# SCH_Orto-Idroponico_2021-11-15.net
KiCad netlist of a schematic drawn in EasyEDA
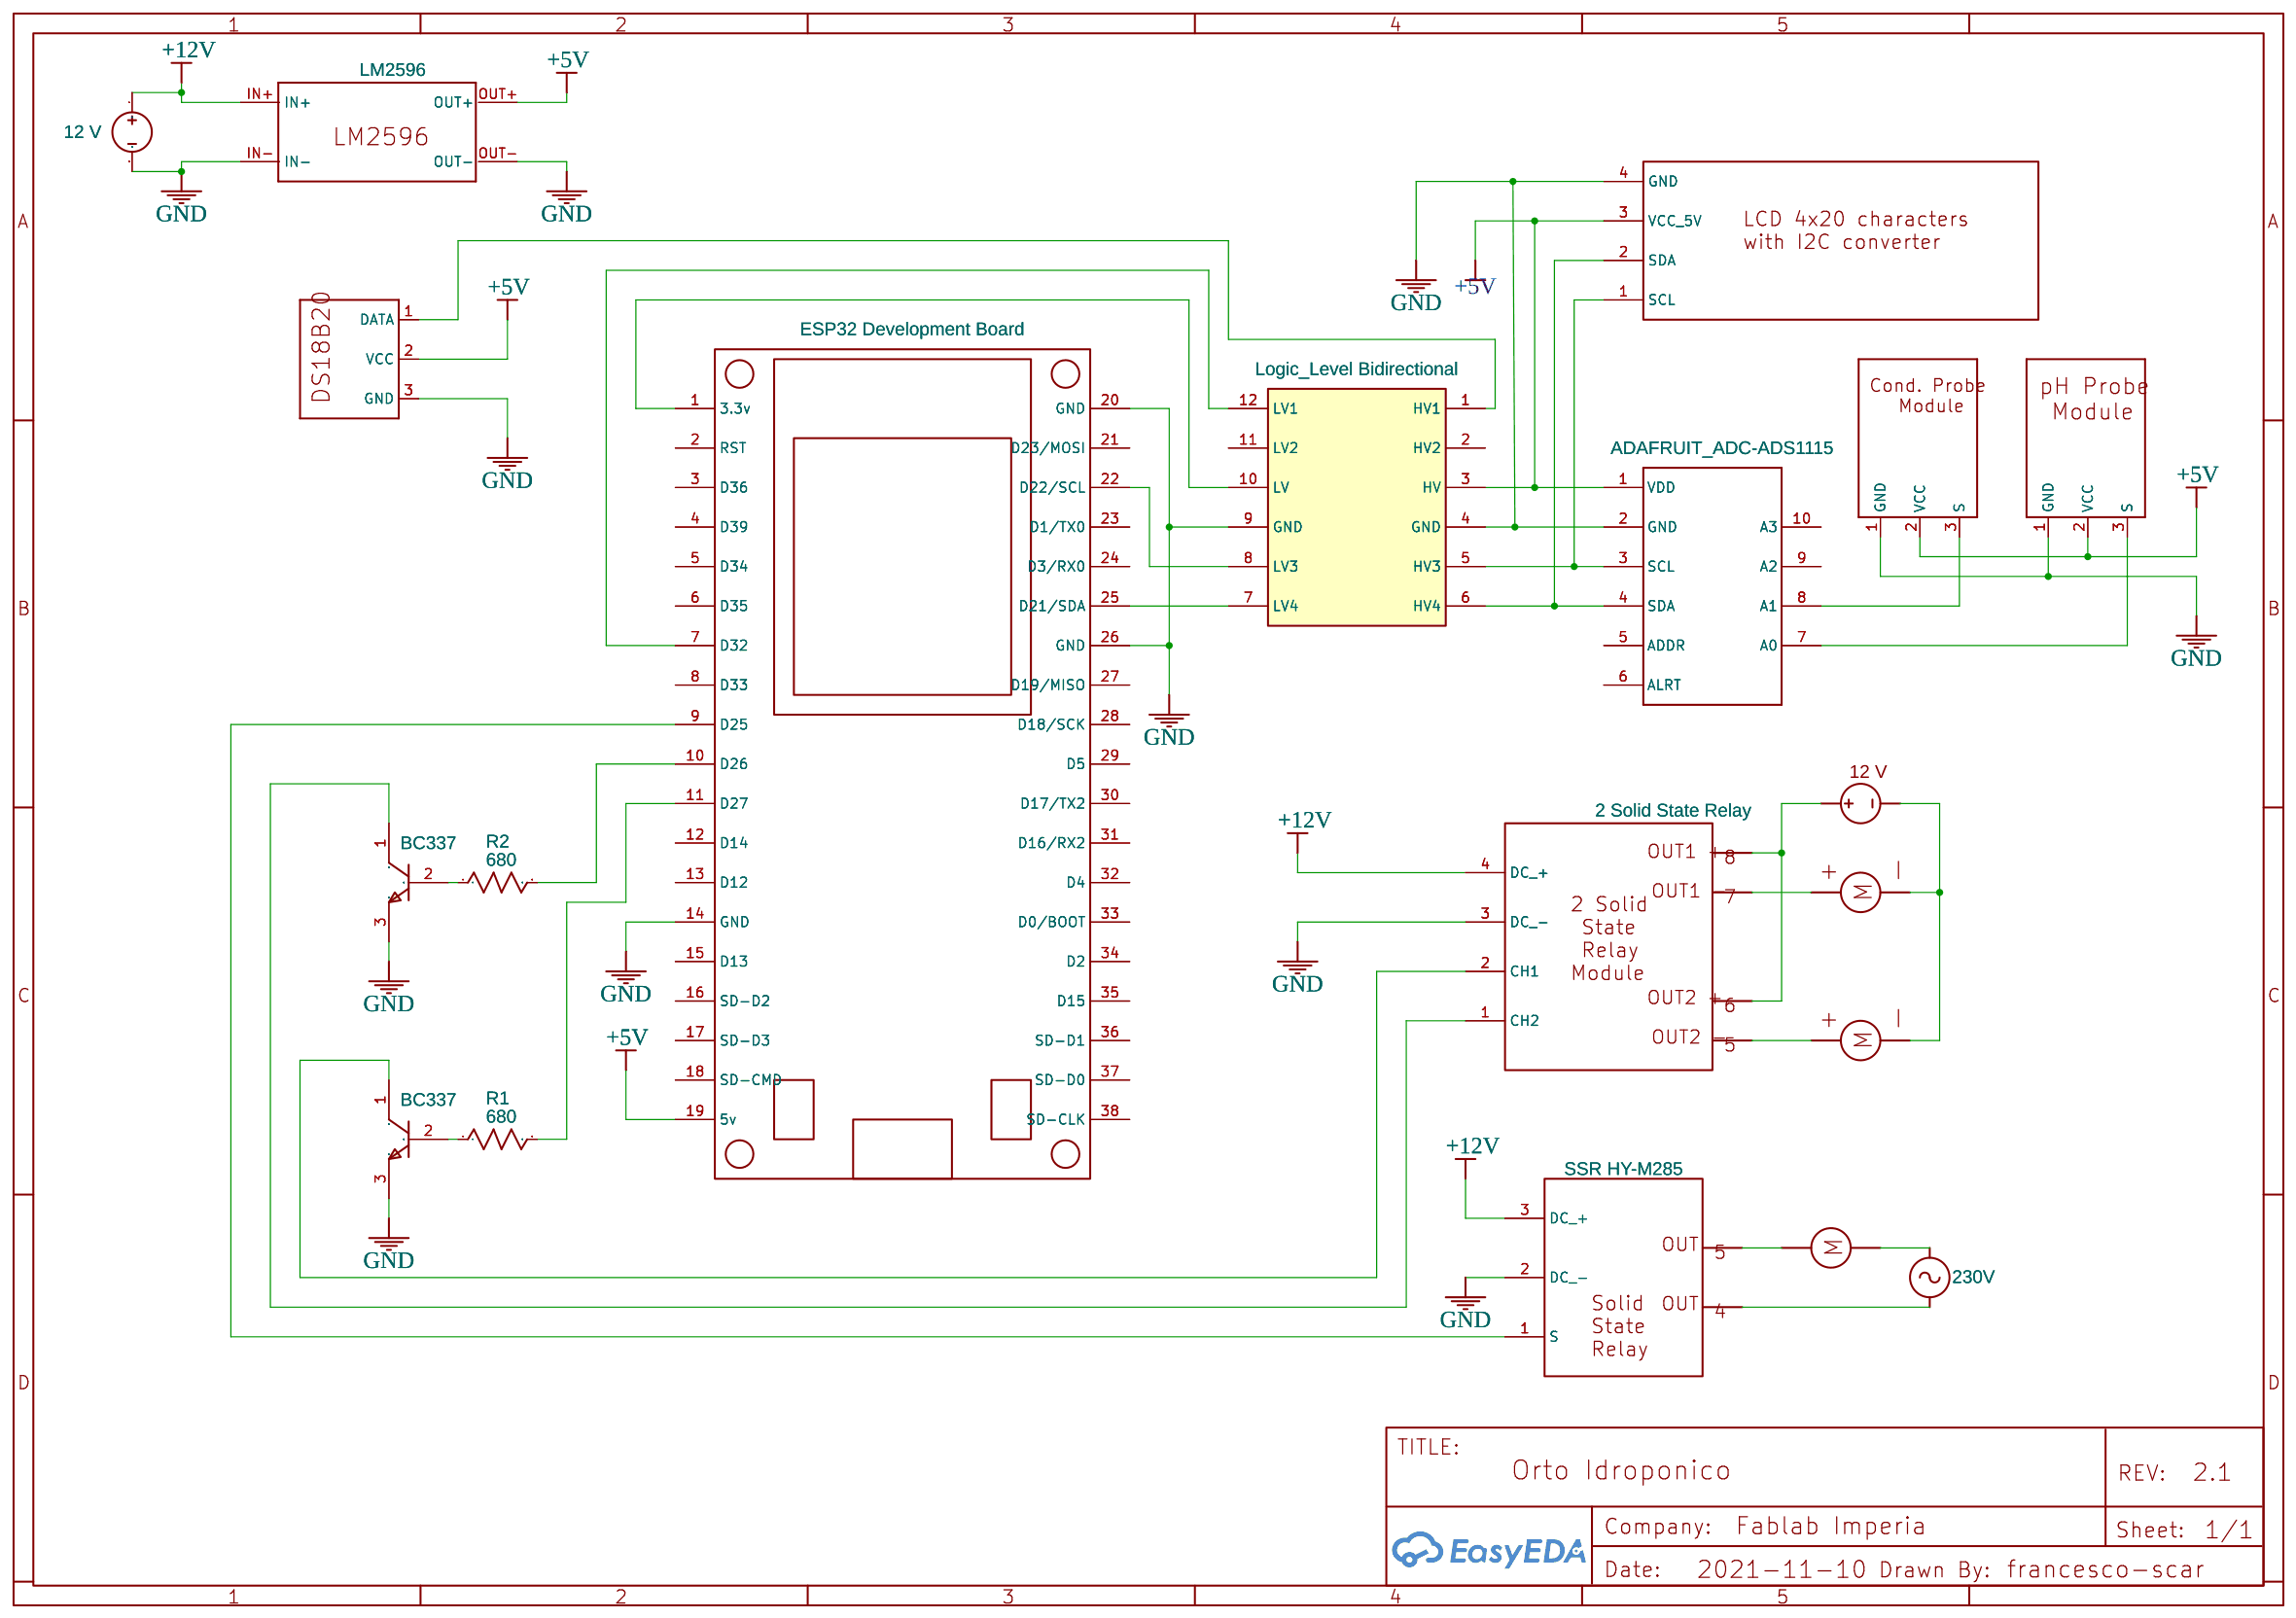
[diagram p0: schematic sheet]

(export (version "E")
  (design (tool "Eeschema 10.0.6"))
  (components
    (comp (ref "2") (value "ADAFRUIT_ADC-ADS1115") (libsource (lib "") (part "ADAFRUIT_ADC-ADS1115")))
    (comp (ref "230V") (value "AC source no pins") (libsource (lib "") (part "AC source no pins")))
    (comp (ref "P2")
      (value "Logic_Level Bidirectional")
      (libsource (lib "") (part "Logic_Level Bidirectional"))
    )
    (comp (ref "Q1") (value "BC337") (libsource (lib "") (part "BC337-40RL1G")))
    (comp (ref "Q2") (value "BC337") (libsource (lib "") (part "BC337-40RL1G")))
    (comp (ref "R1") (value "680") (libsource (lib "") (part "R_AXIAL-1.2_US")))
    (comp (ref "R2") (value "680") (libsource (lib "") (part "R_AXIAL-1.2_US")))
    (comp (ref "REG2") (value "LM2596") (libsource (lib "") (part "LM2596")))
    (comp (ref "T1") (value "DS18B20") (libsource (lib "") (part "DS18B20")))
    (comp (ref "T2") (value "pH probe module") (libsource (lib "") (part "pH probe module")))
    (comp (ref "T3")
      (value "conductivity probe module")
      (libsource (lib "") (part "conductivity probe module"))
    )
    (comp (ref "U1") (value "ESP32 Development Board") (libsource (lib "") (part "ESP32 Development Board")))
    (comp (ref "U2") (value "2 Solid State Relay") (libsource (lib "") (part "2 Solid State Relay")))
    (comp (ref "U3")
      (value "Nettigo LCD 4x20 I2C")
      (fields (field (name "BOM_Manufacturer Part") "2004A"))
      (libsource (lib "") (part "Nettigo LCD 4x20 I2C"))
    )
    (comp (ref "U4") (value "DC power source no pin") (libsource (lib "") (part "DC power source no pin")))
    (comp (ref "U5") (value "SSR HY-M285") (libsource (lib "") (part "Solid State Relay SSR HY-M285")))
    (comp (ref "U7") (value "DC Motor no pin") (libsource (lib "") (part "DC Motor no pin")))
    (comp (ref "U8") (value "DC Motor no pin") (libsource (lib "") (part "DC Motor no pin_1")))
    (comp (ref "U9") (value "DC Motor no pin") (libsource (lib "") (part "DC Motor no pin")))
    (comp (ref "V1") (value "12 V") (libsource (lib "") (part "DC Power Source")))
  )
  (nets
    (net (code "1") (name "+5V") (class "Default")
      (node (ref "2") (pin "1") (pinfunction "VDD_1") (pintype "bidirectional"))
      (node (ref "P2") (pin "3") (pinfunction "HV_3") (pintype "unspecified"))
      (node (ref "REG2") (pin "OUT+") (pinfunction "OUT+_OUT+") (pintype "bidirectional"))
      (node (ref "T1") (pin "2") (pinfunction "VCC_2") (pintype "unspecified"))
      (node (ref "T2") (pin "2") (pinfunction "VCC_2") (pintype "unspecified"))
      (node (ref "T3") (pin "2") (pinfunction "VCC_2") (pintype "unspecified"))
      (node (ref "U1") (pin "19") (pinfunction "5v_19") (pintype "passive"))
      (node (ref "U3") (pin "3") (pinfunction "VCC_5V_3") (pintype "unspecified"))
    )
    (net (code "2") (name "+12V") (class "Default")
      (node (ref "REG2") (pin "IN+") (pinfunction "IN+_IN+") (pintype "bidirectional"))
      (node (ref "U2") (pin "4") (pinfunction "DC_+_4") (pintype "unspecified"))
      (node (ref "U5") (pin "3") (pinfunction "DC_+_3") (pintype "unspecified"))
      (node (ref "V1") (pin "1") (pinfunction "1_1") (pintype "unspecified"))
    )
    (net (code "3") (name "GND") (class "Default")
      (node (ref "2") (pin "2") (pinfunction "GND_2") (pintype "bidirectional"))
      (node (ref "P2") (pin "4") (pinfunction "GND_4") (pintype "unspecified"))
      (node (ref "P2") (pin "9") (pinfunction "GND_9") (pintype "unspecified"))
      (node (ref "Q1") (pin "3") (pinfunction "E_3") (pintype "unspecified"))
      (node (ref "Q2") (pin "3") (pinfunction "E_3") (pintype "unspecified"))
      (node (ref "REG2") (pin "IN-") (pinfunction "IN-_IN-") (pintype "bidirectional"))
      (node (ref "REG2") (pin "OUT-") (pinfunction "OUT-_OUT-") (pintype "bidirectional"))
      (node (ref "T1") (pin "3") (pinfunction "GND_3") (pintype "passive"))
      (node (ref "T2") (pin "1") (pinfunction "GND_1") (pintype "passive"))
      (node (ref "T3") (pin "1") (pinfunction "GND_1") (pintype "passive"))
      (node (ref "U1") (pin "14") (pinfunction "GND_14") (pintype "passive"))
      (node (ref "U1") (pin "20") (pinfunction "GND_20") (pintype "passive"))
      (node (ref "U1") (pin "26") (pinfunction "GND_26") (pintype "passive"))
      (node (ref "U2") (pin "3") (pinfunction "DC_-_3") (pintype "unspecified"))
      (node (ref "U3") (pin "4") (pinfunction "GND_4") (pintype "unspecified"))
      (node (ref "U5") (pin "2") (pinfunction "DC_-_2") (pintype "unspecified"))
      (node (ref "V1") (pin "2") (pinfunction "2_2") (pintype "unspecified"))
    )
    (net (code "4") (name "Net-(2-A0)") (class "Default")
      (node (ref "2") (pin "7") (pinfunction "A0_7") (pintype "bidirectional"))
      (node (ref "T2") (pin "3") (pinfunction "S_3") (pintype "passive"))
    )
    (net (code "5") (name "Net-(2-A1)") (class "Default")
      (node (ref "2") (pin "8") (pinfunction "A1_8") (pintype "bidirectional"))
      (node (ref "T3") (pin "3") (pinfunction "S_3") (pintype "passive"))
    )
    (net (code "6") (name "Net-(2-SCL)") (class "Default")
      (node (ref "2") (pin "3") (pinfunction "SCL_3") (pintype "bidirectional"))
      (node (ref "P2") (pin "5") (pinfunction "HV3_5") (pintype "unspecified"))
      (node (ref "U3") (pin "1") (pinfunction "SCL_1") (pintype "unspecified"))
    )
    (net (code "7") (name "Net-(2-SDA)") (class "Default")
      (node (ref "2") (pin "4") (pinfunction "SDA_4") (pintype "bidirectional"))
      (node (ref "P2") (pin "6") (pinfunction "HV4_6") (pintype "unspecified"))
      (node (ref "U3") (pin "2") (pinfunction "SDA_2") (pintype "unspecified"))
    )
    (net (code "8") (name "Net-(P2-HV1)") (class "Default")
      (node (ref "P2") (pin "1") (pinfunction "HV1_1") (pintype "unspecified"))
      (node (ref "T1") (pin "1") (pinfunction "DATA_1") (pintype "passive"))
    )
    (net (code "9") (name "Net-(P2-LV)") (class "Default")
      (node (ref "P2") (pin "10") (pinfunction "LV_10") (pintype "unspecified"))
      (node (ref "U1") (pin "1") (pinfunction "3.3v_1") (pintype "passive"))
    )
    (net (code "10") (name "Net-(P2-LV1)") (class "Default")
      (node (ref "P2") (pin "12") (pinfunction "LV1_12") (pintype "unspecified"))
      (node (ref "U1") (pin "7") (pinfunction "D32_7") (pintype "bidirectional"))
    )
    (net (code "11") (name "Net-(P2-LV3)") (class "Default")
      (node (ref "P2") (pin "8") (pinfunction "LV3_8") (pintype "unspecified"))
      (node (ref "U1") (pin "22") (pinfunction "D22/SCL_22") (pintype "bidirectional"))
    )
    (net (code "12") (name "Net-(P2-LV4)") (class "Default")
      (node (ref "P2") (pin "7") (pinfunction "LV4_7") (pintype "unspecified"))
      (node (ref "U1") (pin "25") (pinfunction "D21/SDA_25") (pintype "bidirectional"))
    )
    (net (code "13") (name "Net-(Q1-B)") (class "Default")
      (node (ref "Q1") (pin "2") (pinfunction "B_2") (pintype "unspecified"))
      (node (ref "R2") (pin "1") (pinfunction "1_1") (pintype "unspecified"))
    )
    (net (code "14") (name "Net-(Q1-C)") (class "Default")
      (node (ref "Q1") (pin "1") (pinfunction "C_1") (pintype "unspecified"))
      (node (ref "U2") (pin "1") (pinfunction "CH2_1") (pintype "unspecified"))
    )
    (net (code "15") (name "Net-(Q2-B)") (class "Default")
      (node (ref "Q2") (pin "2") (pinfunction "B_2") (pintype "unspecified"))
      (node (ref "R1") (pin "1") (pinfunction "1_1") (pintype "unspecified"))
    )
    (net (code "16") (name "Net-(Q2-C)") (class "Default")
      (node (ref "Q2") (pin "1") (pinfunction "C_1") (pintype "unspecified"))
      (node (ref "U2") (pin "2") (pinfunction "CH1_2") (pintype "unspecified"))
    )
    (net (code "17") (name "Net-(U1-D25)") (class "Default")
      (node (ref "U1") (pin "9") (pinfunction "D25_9") (pintype "bidirectional"))
      (node (ref "U5") (pin "1") (pinfunction "S_1") (pintype "unspecified"))
    )
    (net (code "18") (name "Net-(U1-D26)") (class "Default")
      (node (ref "R2") (pin "2") (pinfunction "2_2") (pintype "unspecified"))
      (node (ref "U1") (pin "10") (pinfunction "D26_10") (pintype "bidirectional"))
    )
    (net (code "19") (name "Net-(U1-D27)") (class "Default")
      (node (ref "R1") (pin "2") (pinfunction "2_2") (pintype "unspecified"))
      (node (ref "U1") (pin "11") (pinfunction "D27_11") (pintype "bidirectional"))
    )
    (net (code "20") (name "unconnected-(2-A2-Pad9)") (class "Default")
      (node (ref "2") (pin "9") (pinfunction "A2_9") (pintype "bidirectional"))
    )
    (net (code "21") (name "unconnected-(2-A3-Pad10)") (class "Default")
      (node (ref "2") (pin "10") (pinfunction "A3_10") (pintype "bidirectional"))
    )
    (net (code "22") (name "unconnected-(2-ADDR-Pad5)") (class "Default")
      (node (ref "2") (pin "5") (pinfunction "ADDR_5") (pintype "bidirectional"))
    )
    (net (code "23") (name "unconnected-(2-ALRT-Pad6)") (class "Default")
      (node (ref "2") (pin "6") (pinfunction "ALRT_6") (pintype "bidirectional"))
    )
    (net (code "24") (name "unconnected-(P2-HV2-Pad2)") (class "Default")
      (node (ref "P2") (pin "2") (pinfunction "HV2_2") (pintype "unspecified"))
    )
    (net (code "25") (name "unconnected-(P2-LV2-Pad11)") (class "Default")
      (node (ref "P2") (pin "11") (pinfunction "LV2_11") (pintype "unspecified"))
    )
    (net (code "26") (name "unconnected-(U1-D0{slash}BOOT-Pad33)") (class "Default")
      (node (ref "U1") (pin "33") (pinfunction "D0/BOOT_33") (pintype "bidirectional"))
    )
    (net (code "27") (name "unconnected-(U1-D1{slash}TX0-Pad23)") (class "Default")
      (node (ref "U1") (pin "23") (pinfunction "D1/TX0_23") (pintype "bidirectional"))
    )
    (net (code "28") (name "unconnected-(U1-D2-Pad34)") (class "Default")
      (node (ref "U1") (pin "34") (pinfunction "D2_34") (pintype "bidirectional"))
    )
    (net (code "29") (name "unconnected-(U1-D3{slash}RX0-Pad24)") (class "Default")
      (node (ref "U1") (pin "24") (pinfunction "D3/RX0_24") (pintype "bidirectional"))
    )
    (net (code "30") (name "unconnected-(U1-D4-Pad32)") (class "Default")
      (node (ref "U1") (pin "32") (pinfunction "D4_32") (pintype "bidirectional"))
    )
    (net (code "31") (name "unconnected-(U1-D5-Pad29)") (class "Default")
      (node (ref "U1") (pin "29") (pinfunction "D5_29") (pintype "bidirectional"))
    )
    (net (code "32") (name "unconnected-(U1-D12-Pad13)") (class "Default")
      (node (ref "U1") (pin "13") (pinfunction "D12_13") (pintype "bidirectional"))
    )
    (net (code "33") (name "unconnected-(U1-D13-Pad15)") (class "Default")
      (node (ref "U1") (pin "15") (pinfunction "D13_15") (pintype "bidirectional"))
    )
    (net (code "34") (name "unconnected-(U1-D14-Pad12)") (class "Default")
      (node (ref "U1") (pin "12") (pinfunction "D14_12") (pintype "bidirectional"))
    )
    (net (code "35") (name "unconnected-(U1-D15-Pad35)") (class "Default")
      (node (ref "U1") (pin "35") (pinfunction "D15_35") (pintype "bidirectional"))
    )
    (net (code "36") (name "unconnected-(U1-D16{slash}RX2-Pad31)") (class "Default")
      (node (ref "U1") (pin "31") (pinfunction "D16/RX2_31") (pintype "bidirectional"))
    )
    (net (code "37") (name "unconnected-(U1-D17{slash}TX2-Pad30)") (class "Default")
      (node (ref "U1") (pin "30") (pinfunction "D17/TX2_30") (pintype "bidirectional"))
    )
    (net (code "38") (name "unconnected-(U1-D18{slash}SCK-Pad28)") (class "Default")
      (node (ref "U1") (pin "28") (pinfunction "D18/SCK_28") (pintype "bidirectional"))
    )
    (net (code "39") (name "unconnected-(U1-D19{slash}MISO-Pad27)") (class "Default")
      (node (ref "U1") (pin "27") (pinfunction "D19/MISO_27") (pintype "bidirectional"))
    )
    (net (code "40") (name "unconnected-(U1-D23{slash}MOSI-Pad21)") (class "Default")
      (node (ref "U1") (pin "21") (pinfunction "D23/MOSI_21") (pintype "bidirectional"))
    )
    (net (code "41") (name "unconnected-(U1-D33-Pad8)") (class "Default")
      (node (ref "U1") (pin "8") (pinfunction "D33_8") (pintype "bidirectional"))
    )
    (net (code "42") (name "unconnected-(U1-D34-Pad5)") (class "Default")
      (node (ref "U1") (pin "5") (pinfunction "D34_5") (pintype "bidirectional"))
    )
    (net (code "43") (name "unconnected-(U1-D35-Pad6)") (class "Default")
      (node (ref "U1") (pin "6") (pinfunction "D35_6") (pintype "bidirectional"))
    )
    (net (code "44") (name "unconnected-(U1-D36-Pad3)") (class "Default")
      (node (ref "U1") (pin "3") (pinfunction "D36_3") (pintype "bidirectional"))
    )
    (net (code "45") (name "unconnected-(U1-D39-Pad4)") (class "Default")
      (node (ref "U1") (pin "4") (pinfunction "D39_4") (pintype "bidirectional"))
    )
    (net (code "46") (name "unconnected-(U1-RST-Pad2)") (class "Default")
      (node (ref "U1") (pin "2") (pinfunction "RST_2") (pintype "bidirectional"))
    )
    (net (code "47") (name "unconnected-(U1-SD-CLK-Pad38)") (class "Default")
      (node (ref "U1") (pin "38") (pinfunction "SD-CLK_38") (pintype "bidirectional"))
    )
    (net (code "48") (name "unconnected-(U1-SD-CMD-Pad18)") (class "Default")
      (node (ref "U1") (pin "18") (pinfunction "SD-CMD_18") (pintype "bidirectional"))
    )
    (net (code "49") (name "unconnected-(U1-SD-D0-Pad37)") (class "Default")
      (node (ref "U1") (pin "37") (pinfunction "SD-D0_37") (pintype "bidirectional"))
    )
    (net (code "50") (name "unconnected-(U1-SD-D1-Pad36)") (class "Default")
      (node (ref "U1") (pin "36") (pinfunction "SD-D1_36") (pintype "bidirectional"))
    )
    (net (code "51") (name "unconnected-(U1-SD-D2-Pad16)") (class "Default")
      (node (ref "U1") (pin "16") (pinfunction "SD-D2_16") (pintype "bidirectional"))
    )
    (net (code "52") (name "unconnected-(U1-SD-D3-Pad17)") (class "Default")
      (node (ref "U1") (pin "17") (pinfunction "SD-D3_17") (pintype "bidirectional"))
    )
  )
)
